# AFF.net
KiCad netlist of a schematic drawn in Altium Designer
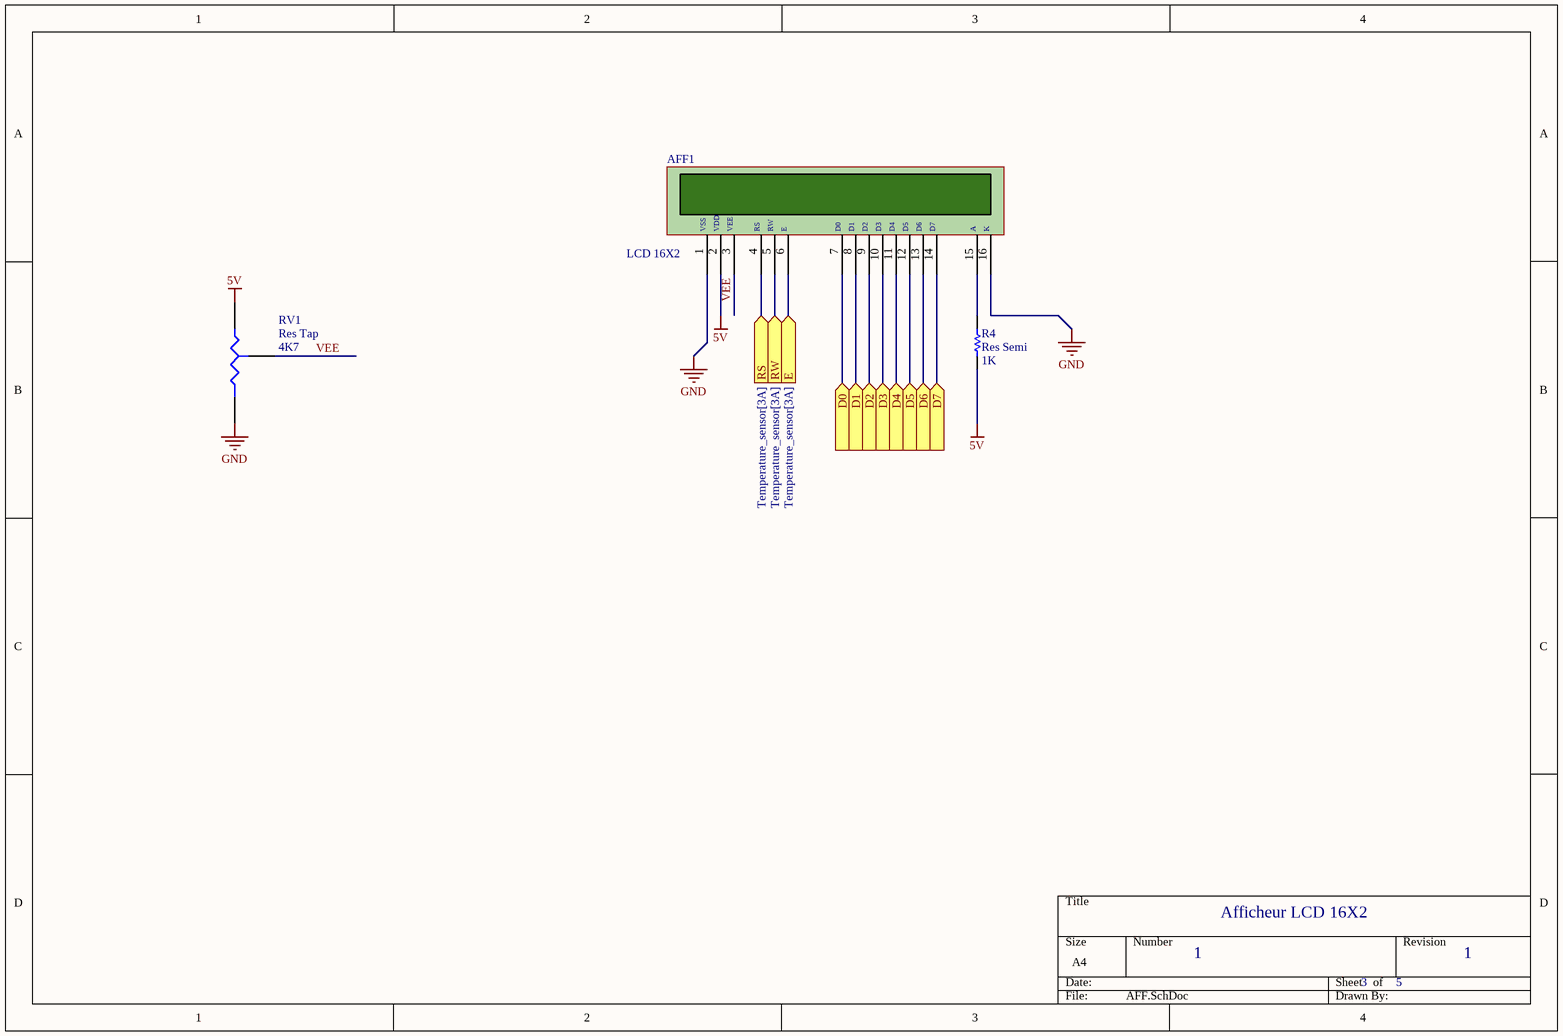
[diagram p0: AFF.SchDoc]

(export (version "E")
  (design (tool "Eeschema 10.0.6"))
  (components
    (comp (ref "AFF1") (value "LCD 16X2") (footprint "lcd 16x2") (libsource (lib "Aff") (part "AFF")))
    (comp (ref "R4")
      (value "Res Semi")
      (footprint "0805")
      (description "Semiconductor Resistor")
      (fields (field (name "ALTIUM_VALUE") "1K") (field (name "PUBLISHER") "Altium Limited"))
      (libsource (lib "Miscellaneous Devices") (part "Res Semi"))
    )
    (comp (ref "RV1")
      (value "Res Tap")
      (footprint "VR3")
      (description "Tapped Resistor")
      (fields (field (name "ALTIUM_VALUE") "4K7") (field (name "PUBLISHER") "Altium Limited"))
      (libsource (lib "Miscellaneous Devices") (part "Res Tap"))
    )
  )
  (nets
    (net (code "1") (name "/D0") (class "Default")
      (node (ref "AFF1") (pin "7") (pinfunction "7_7") (pintype "passive"))
    )
    (net (code "2") (name "/D1") (class "Default")
      (node (ref "AFF1") (pin "8") (pinfunction "8_8") (pintype "passive"))
    )
    (net (code "3") (name "/D2") (class "Default")
      (node (ref "AFF1") (pin "9") (pinfunction "9_9") (pintype "passive"))
    )
    (net (code "4") (name "/D3") (class "Default")
      (node (ref "AFF1") (pin "10") (pinfunction "10_10") (pintype "passive"))
    )
    (net (code "5") (name "/D4") (class "Default")
      (node (ref "AFF1") (pin "11") (pinfunction "11_11") (pintype "passive"))
    )
    (net (code "6") (name "/D5") (class "Default")
      (node (ref "AFF1") (pin "12") (pinfunction "12_12") (pintype "passive"))
    )
    (net (code "7") (name "/D6") (class "Default")
      (node (ref "AFF1") (pin "13") (pinfunction "13_13") (pintype "passive"))
    )
    (net (code "8") (name "/D7") (class "Default")
      (node (ref "AFF1") (pin "14") (pinfunction "14_14") (pintype "passive"))
    )
    (net (code "9") (name "/E") (class "Default")
      (node (ref "AFF1") (pin "6") (pinfunction "6_6") (pintype "passive"))
    )
    (net (code "10") (name "/RS") (class "Default")
      (node (ref "AFF1") (pin "4") (pinfunction "4_4") (pintype "passive"))
    )
    (net (code "11") (name "/RW") (class "Default")
      (node (ref "AFF1") (pin "5") (pinfunction "5_5") (pintype "passive"))
    )
    (net (code "12") (name "/VEE") (class "Default")
      (node (ref "AFF1") (pin "3") (pinfunction "3_3") (pintype "passive"))
      (node (ref "RV1") (pin "3") (pinfunction "TAP_3") (pintype "passive"))
    )
    (net (code "13") (name "5V") (class "Default")
      (node (ref "AFF1") (pin "2") (pinfunction "2_2") (pintype "passive"))
      (node (ref "R4") (pin "1") (pinfunction "1_1") (pintype "passive"))
      (node (ref "RV1") (pin "1") (pinfunction "A_1") (pintype "passive"))
    )
    (net (code "14") (name "GND") (class "Default")
      (node (ref "AFF1") (pin "1") (pinfunction "1_1") (pintype "passive"))
      (node (ref "AFF1") (pin "16") (pinfunction "16_16") (pintype "passive"))
      (node (ref "RV1") (pin "2") (pinfunction "B_2") (pintype "passive"))
    )
    (net (code "15") (name "Net-(AFF1-Pad15)") (class "Default")
      (node (ref "AFF1") (pin "15") (pinfunction "15_15") (pintype "passive"))
      (node (ref "R4") (pin "2") (pinfunction "2_2") (pintype "passive"))
    )
  )
)
